# POWR0001_BCR_LT1513.net
KiCad netlist of a schematic drawn in Altium Designer
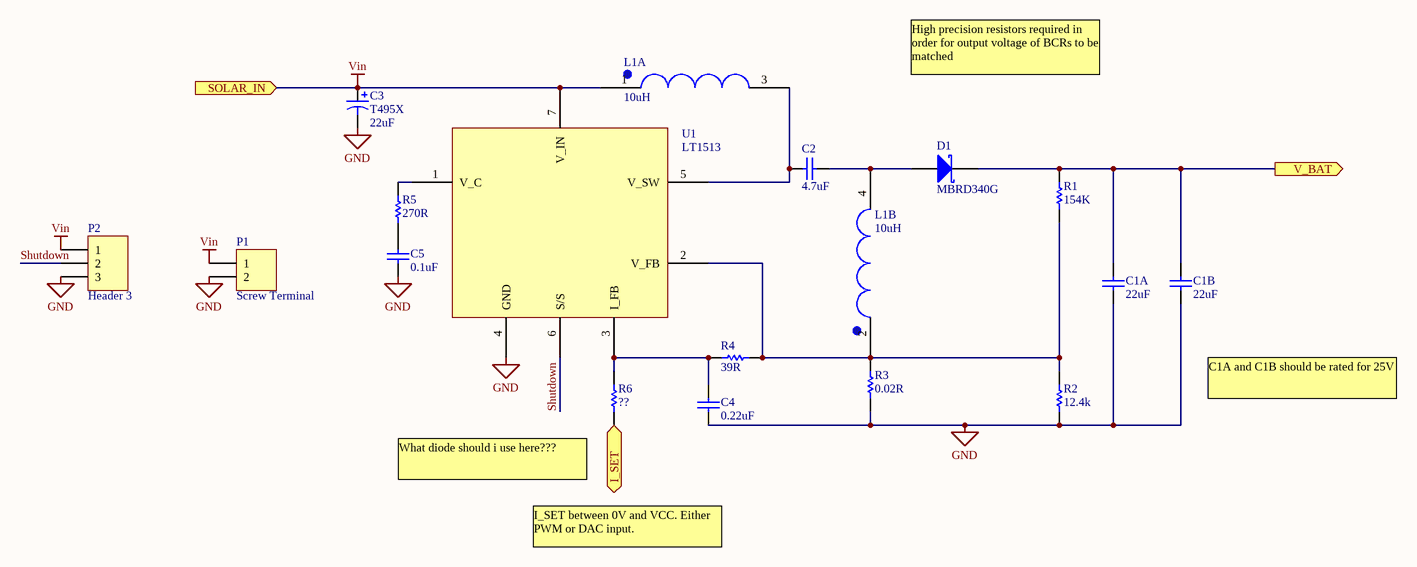
[diagram p0: POWR0001_BCR_LT1513.SchDoc]

(export (version "E")
  (design (tool "Eeschema 10.0.6"))
  (components
    (comp (ref "C1A")
      (value "22uF")
      (footprint "CAPC3225M")
      (description "Capacitor")
      (fields (field (name "Comment") "Cap") (field (name "PUBLISHER") "Altium Limited"))
      (libsource (lib "Miscellaneous Devices") (part "Cap"))
    )
    (comp (ref "C1B")
      (value "22uF")
      (footprint "CAPC3225M")
      (description "Capacitor")
      (fields (field (name "Comment") "Cap") (field (name "PUBLISHER") "Altium Limited"))
      (libsource (lib "Miscellaneous Devices") (part "Cap"))
    )
    (comp (ref "C2")
      (value "4.7uF")
      (footprint "CAPC3225M")
      (description "Capacitor")
      (fields (field (name "Comment") "Cap") (field (name "PUBLISHER") "Altium Limited"))
      (libsource (lib "Miscellaneous Devices") (part "Cap"))
    )
    (comp (ref "C3")
      (value "T495X")
      (footprint "X")
      (description "Solid Tantalum Chip Capacitor, Standard T495 Series - Low ESR, Surge Robust")
      (fields (field (name "ALTIUM_VALUE") "22uF") (field (name "PUBLISHER") "Altium Limited"))
      (libsource (lib "KEMET Chip Capacitor") (part "T495X"))
    )
    (comp (ref "C4")
      (value "0.22uF")
      (footprint "CAPC3216M")
      (description "Capacitor")
      (fields (field (name "Comment") "Cap") (field (name "PUBLISHER") "Altium Limited"))
      (libsource (lib "Miscellaneous Devices") (part "Cap"))
    )
    (comp (ref "C5")
      (value "0.1uF")
      (footprint "CAPC3216M")
      (description "Capacitor")
      (fields (field (name "Comment") "Cap") (field (name "PUBLISHER") "Altium Limited"))
      (libsource (lib "Miscellaneous Devices") (part "Cap"))
    )
    (comp (ref "D1")
      (value "MBRD340G")
      (footprint "TO229P990X238-3N")
      (description "Schottky Rectifier")
      (fields (field (name "PUBLISHER") "Altium Limited"))
      (libsource (lib "Miscellaneous Devices") (part "Diode 11DQ03"))
    )
    (comp (ref "L1")
      (value "10uH")
      (footprint "DRQ125")
      (fields (field (name "Comment") "DRQ125 Dual Inductor"))
      (libsource (lib "LT1513") (part "DRQ125 Dual Inductor"))
    )
    (comp (ref "P1")
      (value "Screw Terminal")
      (footprint "Screw Header 2")
      (description "Header, 2-Pin")
      (fields (field (name "PUBLISHER") "Altium Limited"))
      (libsource (lib "Miscellaneous Connectors") (part "Header 2"))
    )
    (comp (ref "P2")
      (value "Header 3")
      (footprint "HDR1X3")
      (description "Header, 3-Pin")
      (fields (field (name "PUBLISHER") "Altium Limited"))
      (libsource (lib "Miscellaneous Connectors") (part "Header 3"))
    )
    (comp (ref "R1")
      (value "154K")
      (footprint "RESC3216M")
      (description "Resistor")
      (fields (field (name "Comment") "Res1") (field (name "PUBLISHER") "Altium Limited"))
      (libsource (lib "Miscellaneous Devices") (part "Res1"))
    )
    (comp (ref "R2")
      (value "12.4k")
      (footprint "RESC3216M")
      (description "Resistor")
      (fields (field (name "Comment") "Res1") (field (name "PUBLISHER") "Altium Limited"))
      (libsource (lib "Miscellaneous Devices") (part "Res1"))
    )
    (comp (ref "R3")
      (value "0.02R")
      (footprint "RESC3216M")
      (description "Resistor")
      (fields (field (name "Comment") "Res1") (field (name "PUBLISHER") "Altium Limited"))
      (libsource (lib "Miscellaneous Devices") (part "Res1"))
    )
    (comp (ref "R4")
      (value "39R")
      (footprint "RESC3216M")
      (description "Resistor")
      (fields (field (name "Comment") "Res1") (field (name "PUBLISHER") "Altium Limited"))
      (libsource (lib "Miscellaneous Devices") (part "Res1"))
    )
    (comp (ref "R5")
      (value "270R")
      (footprint "RESC3216M")
      (description "Resistor")
      (fields (field (name "Comment") "Res1") (field (name "PUBLISHER") "Altium Limited"))
      (libsource (lib "Miscellaneous Devices") (part "Res1"))
    )
    (comp (ref "R6")
      (value "??")
      (footprint "RESC3216M")
      (description "Resistor")
      (fields (field (name "Comment") "Res1") (field (name "PUBLISHER") "Altium Limited"))
      (libsource (lib "Miscellaneous Devices") (part "Res1"))
    )
    (comp (ref "U1")
      (value "LT1513")
      (footprint "TO152P1396X238-8N")
      (libsource (lib "LT1513") (part "LT1513"))
    )
  )
  (nets
    (net (code "1") (name "/I_SET") (class "Default")
      (node (ref "R6") (pin "2") (pinfunction "2_2") (pintype "passive"))
    )
    (net (code "2") (name "/Shutdown") (class "Default")
      (node (ref "P2") (pin "2") (pinfunction "2_2") (pintype "passive"))
      (node (ref "U1") (pin "6") (pinfunction "S/S_6") (pintype "passive"))
    )
    (net (code "3") (name "/V_BAT") (class "Default")
      (node (ref "C1A") (pin "1") (pinfunction "1_1") (pintype "passive"))
      (node (ref "C1B") (pin "1") (pinfunction "1_1") (pintype "passive"))
      (node (ref "D1") (pin "2") (pinfunction "K_2") (pintype "passive"))
      (node (ref "R1") (pin "2") (pinfunction "2_2") (pintype "passive"))
    )
    (net (code "4") (name "GND") (class "Default")
      (node (ref "C1A") (pin "2") (pinfunction "2_2") (pintype "passive"))
      (node (ref "C1B") (pin "2") (pinfunction "2_2") (pintype "passive"))
      (node (ref "C3") (pin "2") (pinfunction "2_2") (pintype "passive"))
      (node (ref "C4") (pin "2") (pinfunction "2_2") (pintype "passive"))
      (node (ref "C5") (pin "2") (pinfunction "2_2") (pintype "passive"))
      (node (ref "P1") (pin "2") (pinfunction "2_2") (pintype "passive"))
      (node (ref "P2") (pin "3") (pinfunction "3_3") (pintype "passive"))
      (node (ref "R2") (pin "1") (pinfunction "1_1") (pintype "passive"))
      (node (ref "R3") (pin "1") (pinfunction "1_1") (pintype "passive"))
      (node (ref "U1") (pin "4") (pinfunction "GND_4") (pintype "passive"))
    )
    (net (code "5") (name "Net-(C5-Pad1)") (class "Default")
      (node (ref "C5") (pin "1") (pinfunction "1_1") (pintype "passive"))
      (node (ref "R5") (pin "2") (pinfunction "2_2") (pintype "passive"))
    )
    (net (code "6") (name "Net-(D1-A)") (class "Default")
      (node (ref "C2") (pin "1") (pinfunction "1_1") (pintype "passive"))
      (node (ref "D1") (pin "1") (pinfunction "A_1") (pintype "passive"))
      (node (ref "L1") (pin "4") (pinfunction "18_4") (pintype "passive"))
    )
    (net (code "7") (name "Net-(L1A-18)") (class "Default")
      (node (ref "C2") (pin "2") (pinfunction "2_2") (pintype "passive"))
      (node (ref "L1") (pin "3") (pinfunction "18_3") (pintype "passive"))
      (node (ref "U1") (pin "5") (pinfunction "V_SW_5") (pintype "passive"))
    )
    (net (code "8") (name "Net-(L1B-17)") (class "Default")
      (node (ref "L1") (pin "2") (pinfunction "17_2") (pintype "passive"))
      (node (ref "R1") (pin "1") (pinfunction "1_1") (pintype "passive"))
      (node (ref "R2") (pin "2") (pinfunction "2_2") (pintype "passive"))
      (node (ref "R3") (pin "2") (pinfunction "2_2") (pintype "passive"))
      (node (ref "R4") (pin "1") (pinfunction "1_1") (pintype "passive"))
      (node (ref "U1") (pin "2") (pinfunction "V_FB_2") (pintype "passive"))
    )
    (net (code "9") (name "Net-(U1-I_FB)") (class "Default")
      (node (ref "C4") (pin "1") (pinfunction "1_1") (pintype "passive"))
      (node (ref "R4") (pin "2") (pinfunction "2_2") (pintype "passive"))
      (node (ref "R6") (pin "1") (pinfunction "1_1") (pintype "passive"))
      (node (ref "U1") (pin "3") (pinfunction "I_FB_3") (pintype "passive"))
    )
    (net (code "10") (name "Net-(U1-V_C)") (class "Default")
      (node (ref "R5") (pin "1") (pinfunction "1_1") (pintype "passive"))
      (node (ref "U1") (pin "1") (pinfunction "V_C_1") (pintype "passive"))
    )
    (net (code "11") (name "Vin") (class "Default")
      (node (ref "C3") (pin "1") (pinfunction "1_1") (pintype "passive"))
      (node (ref "L1") (pin "1") (pinfunction "17_1") (pintype "passive"))
      (node (ref "P1") (pin "1") (pinfunction "1_1") (pintype "passive"))
      (node (ref "P2") (pin "1") (pinfunction "1_1") (pintype "passive"))
      (node (ref "U1") (pin "7") (pinfunction "V_IN_7") (pintype "passive"))
    )
  )
)
